# USB2TTL.net
KiCad netlist of a schematic drawn in EAGLE
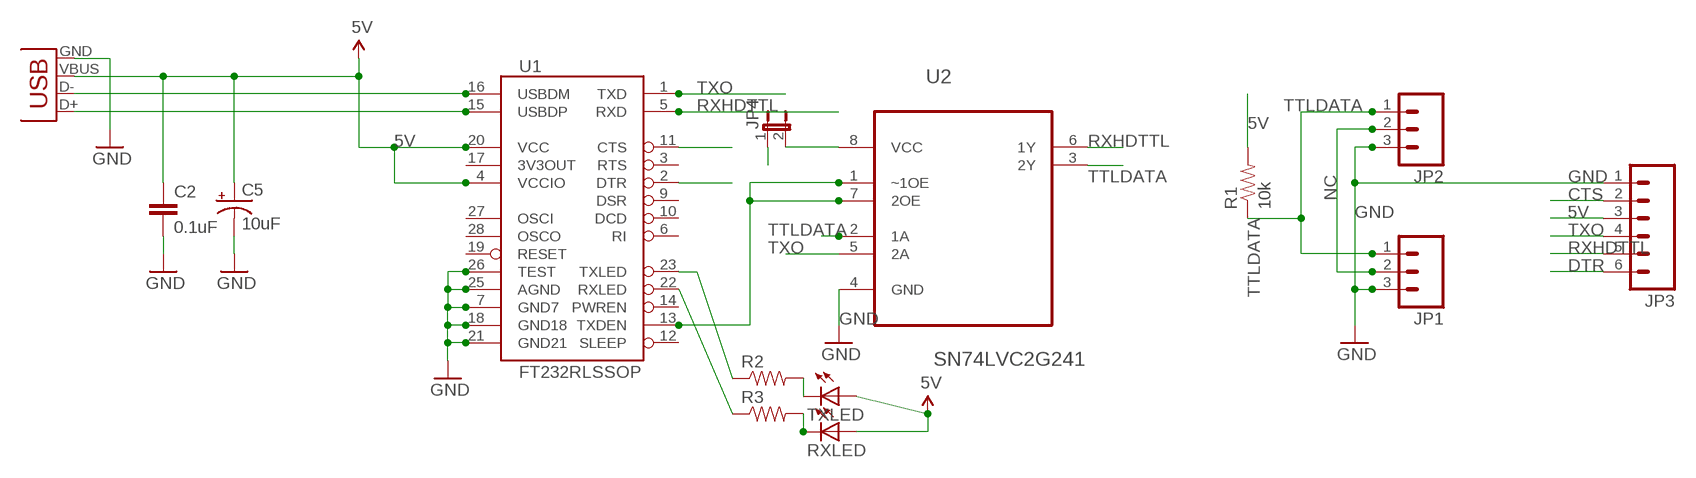
[diagram p0: schematic, sheet 1]

(export (version "E")
  (design (tool "Eeschema 10.0.6"))
  (components
    (comp (ref "C2")
      (value "0.1uF")
      (footprint "eagle-import:0402-CAP")
      (libsource (lib "eagle-import") (part "CAP0402-CAP"))
    )
    (comp (ref "C5")
      (value "10uF")
      (footprint "eagle-import:EIA3216")
      (libsource (lib "eagle-import") (part "CAP_POL1206"))
    )
    (comp (ref "JP1")
      (value "M03LOCK_LONGPADS")
      (footprint "eagle-import:1X03_LOCK_LONGPADS")
      (libsource (lib "eagle-import") (part "M03LOCK_LONGPADS"))
    )
    (comp (ref "JP2")
      (value "M03LOCK_LONGPADS")
      (footprint "eagle-import:1X03_LOCK_LONGPADS")
      (libsource (lib "eagle-import") (part "M03LOCK_LONGPADS"))
    )
    (comp (ref "JP3")
      (value "M06LOCK")
      (footprint "eagle-import:1X06_LOCK")
      (libsource (lib "eagle-import") (part "M06LOCK"))
    )
    (comp (ref "JP4")
      (value "JUMPER-2-OLDSMD-NO")
      (footprint "eagle-import:SJ_2S-NO")
      (libsource (lib "eagle-import") (part "JUMPER-2-OLDSMD-NO"))
    )
    (comp (ref "R1")
      (value "10k")
      (footprint "eagle-import:0603-RES")
      (libsource (lib "eagle-import") (part "custom-cap0603_RESISTOR0603-RES"))
    )
    (comp (ref "R2")
      (value "RESISTOR0603-RES")
      (footprint "eagle-import:0603-RES")
      (libsource (lib "eagle-import") (part "RESISTOR0603-RES"))
    )
    (comp (ref "R3")
      (value "RESISTOR0603-RES")
      (footprint "eagle-import:0603-RES")
      (libsource (lib "eagle-import") (part "RESISTOR0603-RES"))
    )
    (comp (ref "RXLED")
      (value "LED0603")
      (footprint "eagle-import:LED-0603")
      (libsource (lib "eagle-import") (part "LED0603"))
    )
    (comp (ref "TXLED")
      (value "LED0603")
      (footprint "eagle-import:LED-0603")
      (libsource (lib "eagle-import") (part "LED0603"))
    )
    (comp (ref "U1")
      (value "FT232RLSSOP")
      (footprint "eagle-import:SSOP28DB")
      (libsource (lib "eagle-import") (part "FT232RLSSOP"))
    )
    (comp (ref "U2")
      (value "SN74LVC2G241")
      (footprint "eagle-import:SOP65P400X130-8N")
      (libsource (lib "eagle-import") (part "SN74LVC2G241"))
    )
    (comp (ref "X2")
      (value "USB-SMD-NS")
      (footprint "eagle-import:USB-MINIB-NOSTOP")
      (libsource (lib "eagle-import") (part "USB-SMD-NS"))
    )
  )
  (nets
    (net (code "1") (name "/CTS") (class "Default")
      (node (ref "JP3") (pin "2") (pinfunction "2_2") (pintype "passive"))
      (node (ref "U1") (pin "11") (pinfunction "CTS_11") (pintype "input"))
    )
    (net (code "2") (name "/DTR") (class "Default")
      (node (ref "JP3") (pin "6") (pinfunction "6_6") (pintype "passive"))
      (node (ref "U1") (pin "2") (pinfunction "DTR_2") (pintype "output"))
    )
    (net (code "3") (name "/NC") (class "Default")
      (node (ref "JP1") (pin "2") (pinfunction "2_2") (pintype "passive"))
      (node (ref "JP2") (pin "2") (pinfunction "2_2") (pintype "passive"))
    )
    (net (code "4") (name "/RXHDTTL") (class "Default")
      (node (ref "JP3") (pin "5") (pinfunction "5_5") (pintype "passive"))
      (node (ref "U1") (pin "5") (pinfunction "RXD_5") (pintype "input"))
      (node (ref "U2") (pin "6") (pinfunction "1Y_6") (pintype "output"))
    )
    (net (code "5") (name "/TTLDATA") (class "Default")
      (node (ref "JP1") (pin "1") (pinfunction "1_1") (pintype "passive"))
      (node (ref "JP2") (pin "1") (pinfunction "1_1") (pintype "passive"))
      (node (ref "R1") (pin "1") (pinfunction "1_1") (pintype "passive"))
      (node (ref "U2") (pin "2") (pinfunction "1A_2") (pintype "input"))
      (node (ref "U2") (pin "3") (pinfunction "2Y_3") (pintype "output"))
    )
    (net (code "6") (name "/TXO") (class "Default")
      (node (ref "JP3") (pin "4") (pinfunction "4_4") (pintype "passive"))
      (node (ref "U1") (pin "1") (pinfunction "TXD_1") (pintype "output"))
      (node (ref "U2") (pin "5") (pinfunction "2A_5") (pintype "input"))
    )
    (net (code "7") (name "5V") (class "Default")
      (node (ref "C2") (pin "1") (pinfunction "1_1") (pintype "passive"))
      (node (ref "C5") (pin "A") (pinfunction "+_A") (pintype "passive"))
      (node (ref "JP3") (pin "3") (pinfunction "3_3") (pintype "passive"))
      (node (ref "JP4") (pin "1") (pinfunction "1_1") (pintype "passive"))
      (node (ref "R1") (pin "2") (pinfunction "2_2") (pintype "passive"))
      (node (ref "RXLED") (pin "A") (pinfunction "A_A") (pintype "passive"))
      (node (ref "TXLED") (pin "A") (pinfunction "A_A") (pintype "passive"))
      (node (ref "U1") (pin "20") (pinfunction "VCC_20") (pintype "power_in"))
      (node (ref "U1") (pin "4") (pinfunction "VCCIO_4") (pintype "power_in"))
      (node (ref "X2") (pin "VBUS") (pinfunction "VBUS_VBUS") (pintype "bidirectional"))
    )
    (net (code "8") (name "GND") (class "Default")
      (node (ref "C2") (pin "2") (pinfunction "2_2") (pintype "passive"))
      (node (ref "C5") (pin "C") (pinfunction "-_C") (pintype "passive"))
      (node (ref "JP1") (pin "3") (pinfunction "3_3") (pintype "passive"))
      (node (ref "JP2") (pin "3") (pinfunction "3_3") (pintype "passive"))
      (node (ref "JP3") (pin "1") (pinfunction "1_1") (pintype "passive"))
      (node (ref "U1") (pin "18") (pinfunction "GND18_18") (pintype "power_in"))
      (node (ref "U1") (pin "21") (pinfunction "GND21_21") (pintype "power_in"))
      (node (ref "U1") (pin "25") (pinfunction "AGND_25") (pintype "power_in"))
      (node (ref "U1") (pin "26") (pinfunction "TEST_26") (pintype "input"))
      (node (ref "U1") (pin "7") (pinfunction "GND7_7") (pintype "power_in"))
      (node (ref "U2") (pin "4") (pinfunction "GND_4") (pintype "passive"))
      (node (ref "X2") (pin "GND") (pinfunction "GND_GND") (pintype "bidirectional"))
    )
    (net (code "9") (name "Net-(R2-Pad2)") (class "Default")
      (node (ref "R2") (pin "2") (pinfunction "2_2") (pintype "passive"))
      (node (ref "TXLED") (pin "C") (pinfunction "C_C") (pintype "passive"))
    )
    (net (code "10") (name "Net-(R3-Pad2)") (class "Default")
      (node (ref "R3") (pin "2") (pinfunction "2_2") (pintype "passive"))
      (node (ref "RXLED") (pin "C") (pinfunction "C_C") (pintype "passive"))
    )
    (net (code "11") (name "Net-(U1-RXLED)") (class "Default")
      (node (ref "R3") (pin "1") (pinfunction "1_1") (pintype "passive"))
      (node (ref "U1") (pin "22") (pinfunction "RXLED_22") (pintype "input"))
    )
    (net (code "12") (name "Net-(U1-TXDEN)") (class "Default")
      (node (ref "U1") (pin "13") (pinfunction "TXDEN_13") (pintype "input"))
      (node (ref "U2") (pin "1") (pinfunction "~{1OE}_1") (pintype "input"))
      (node (ref "U2") (pin "7") (pinfunction "2OE_7") (pintype "input"))
    )
    (net (code "13") (name "Net-(U1-TXLED)") (class "Default")
      (node (ref "R2") (pin "1") (pinfunction "1_1") (pintype "passive"))
      (node (ref "U1") (pin "23") (pinfunction "TXLED_23") (pintype "input"))
    )
    (net (code "14") (name "Net-(U1-USBDM)") (class "Default")
      (node (ref "U1") (pin "16") (pinfunction "USBDM_16") (pintype "bidirectional"))
      (node (ref "X2") (pin "D-") (pinfunction "D-_D-") (pintype "bidirectional"))
    )
    (net (code "15") (name "Net-(U1-USBDP)") (class "Default")
      (node (ref "U1") (pin "15") (pinfunction "USBDP_15") (pintype "bidirectional"))
      (node (ref "X2") (pin "D+") (pinfunction "D+_D+") (pintype "bidirectional"))
    )
    (net (code "16") (name "Net-(U2-VCC)") (class "Default")
      (node (ref "JP4") (pin "2") (pinfunction "2_2") (pintype "passive"))
      (node (ref "U2") (pin "8") (pinfunction "VCC_8") (pintype "power_in"))
    )
    (net (code "17") (name "unconnected-(U1-3V3OUT-Pad17)") (class "Default")
      (node (ref "U1") (pin "17") (pinfunction "3V3OUT_17") (pintype "output"))
    )
    (net (code "18") (name "unconnected-(U1-DCD-Pad10)") (class "Default")
      (node (ref "U1") (pin "10") (pinfunction "DCD_10") (pintype "input"))
    )
    (net (code "19") (name "unconnected-(U1-DSR-Pad9)") (class "Default")
      (node (ref "U1") (pin "9") (pinfunction "DSR_9") (pintype "input"))
    )
    (net (code "20") (name "unconnected-(U1-OSCI-Pad27)") (class "Default")
      (node (ref "U1") (pin "27") (pinfunction "OSCI_27") (pintype "input"))
    )
    (net (code "21") (name "unconnected-(U1-OSCO-Pad28)") (class "Default")
      (node (ref "U1") (pin "28") (pinfunction "OSCO_28") (pintype "output"))
    )
    (net (code "22") (name "unconnected-(U1-PWREN-Pad14)") (class "Default")
      (node (ref "U1") (pin "14") (pinfunction "PWREN_14") (pintype "input"))
    )
    (net (code "23") (name "unconnected-(U1-RESET-Pad19)") (class "Default")
      (node (ref "U1") (pin "19") (pinfunction "RESET_19") (pintype "input"))
    )
    (net (code "24") (name "unconnected-(U1-RI-Pad6)") (class "Default")
      (node (ref "U1") (pin "6") (pinfunction "RI_6") (pintype "input"))
    )
    (net (code "25") (name "unconnected-(U1-RTS-Pad3)") (class "Default")
      (node (ref "U1") (pin "3") (pinfunction "RTS_3") (pintype "output"))
    )
    (net (code "26") (name "unconnected-(U1-SLEEP-Pad12)") (class "Default")
      (node (ref "U1") (pin "12") (pinfunction "SLEEP_12") (pintype "input"))
    )
  )
)
